# USB2CAN.net
KiCad netlist of a schematic drawn in Altium Designer
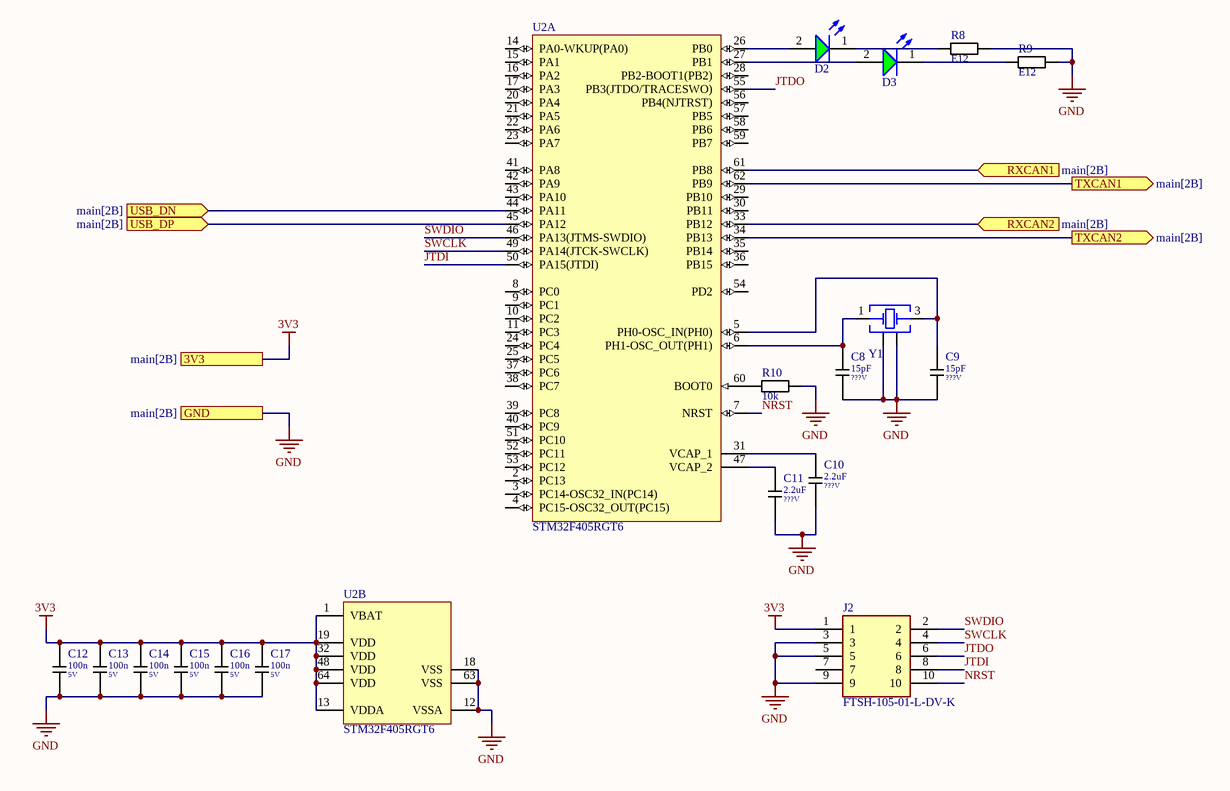
[diagram p0: USB2CAN.SchDoc]

(export (version "E")
  (design (tool "Eeschema 10.0.6"))
  (components
    (comp (ref "C8")
      (value "15pF")
      (footprint "0603_C")
      (description "Keramikkondensatoren 0603")
      (fields (field (name "SPG") "???V") (field (name "Comment") "15pF_???V"))
      (libsource (lib "Allgemeine_ETI_Schematic_Lib") (part "C_0603_Keramik"))
    )
    (comp (ref "C9")
      (value "15pF")
      (footprint "0603_C")
      (description "Keramikkondensatoren 0603")
      (fields (field (name "SPG") "???V") (field (name "Comment") "15pF_???V"))
      (libsource (lib "Allgemeine_ETI_Schematic_Lib") (part "C_0603_Keramik"))
    )
    (comp (ref "C10")
      (value "2.2uF")
      (footprint "0603_C")
      (description "Keramikkondensatoren 0603")
      (fields (field (name "SPG") "???V") (field (name "Comment") "2.2uF_???V"))
      (libsource (lib "Allgemeine_ETI_Schematic_Lib") (part "C_0603_Keramik"))
    )
    (comp (ref "C11")
      (value "2.2uF")
      (footprint "0603_C")
      (description "Keramikkondensatoren 0603")
      (fields (field (name "SPG") "???V") (field (name "Comment") "2.2uF_???V"))
      (libsource (lib "Allgemeine_ETI_Schematic_Lib") (part "C_0603_Keramik"))
    )
    (comp (ref "C12")
      (value "100n")
      (footprint "0603_C")
      (description "Keramikkondensatoren 0603")
      (fields (field (name "SPG") "5V") (field (name "Comment") "100n_5V"))
      (libsource (lib "Allgemeine_ETI_Schematic_Lib") (part "C_0603_Keramik"))
    )
    (comp (ref "C13")
      (value "100n")
      (footprint "0603_C")
      (description "Keramikkondensatoren 0603")
      (fields (field (name "SPG") "5V") (field (name "Comment") "100n_5V"))
      (libsource (lib "Allgemeine_ETI_Schematic_Lib") (part "C_0603_Keramik"))
    )
    (comp (ref "C14")
      (value "100n")
      (footprint "0603_C")
      (description "Keramikkondensatoren 0603")
      (fields (field (name "SPG") "5V") (field (name "Comment") "100n_5V"))
      (libsource (lib "Allgemeine_ETI_Schematic_Lib") (part "C_0603_Keramik"))
    )
    (comp (ref "C15")
      (value "100n")
      (footprint "0603_C")
      (description "Keramikkondensatoren 0603")
      (fields (field (name "SPG") "5V") (field (name "Comment") "100n_5V"))
      (libsource (lib "Allgemeine_ETI_Schematic_Lib") (part "C_0603_Keramik"))
    )
    (comp (ref "C16")
      (value "100n")
      (footprint "0603_C")
      (description "Keramikkondensatoren 0603")
      (fields (field (name "SPG") "5V") (field (name "Comment") "100n_5V"))
      (libsource (lib "Allgemeine_ETI_Schematic_Lib") (part "C_0603_Keramik"))
    )
    (comp (ref "C17")
      (value "100n")
      (footprint "0603_C")
      (description "Keramikkondensatoren 0603")
      (fields (field (name "SPG") "5V") (field (name "Comment") "100n_5V"))
      (libsource (lib "Allgemeine_ETI_Schematic_Lib") (part "C_0603_Keramik"))
    )
    (comp (ref "D2")
      (value "Bright Green, 2V, 140°")
      (footprint "WL-SMCD_0603")
      (description "WL-SMCD Mono-color Chip LED Diffused, SMT, size 0603, Bright Green, 2V, 140°")
      (fields
        (field (name "MANUFACTURER PART NUMBER") "150060VS55040")
        (field (name "MANUFACTURER") "Wurth Elektronik")
      )
      (libsource (lib "Altium_WL-SMCD (rev24a)") (part "150060VS55040"))
    )
    (comp (ref "D3")
      (value "Bright Green, 2V, 140°")
      (footprint "WL-SMCD_0603")
      (description "WL-SMCD Mono-color Chip LED Diffused, SMT, size 0603, Bright Green, 2V, 140°")
      (fields
        (field (name "MANUFACTURER PART NUMBER") "150060VS55040")
        (field (name "MANUFACTURER") "Wurth Elektronik")
      )
      (libsource (lib "Altium_WL-SMCD (rev24a)") (part "150060VS55040"))
    )
    (comp (ref "J2")
      (value "FTSH-105-01-L-DV-K")
      (footprint "FTSH10501LDVK:FTSH10501LDVK")
      (description "Samtec, FTSH, 10 Way, 2 Row, Straight Pin Header")
      (fields (field (name "MOUSER PART NUMBER") "200-FTSH10501LDVK"))
      (libsource (lib "FTSH-105-01-L-DV-K") (part "FTSH-105-01-L-DV-K"))
    )
    (comp (ref "R8")
      (value "E12")
      (footprint "0603_R")
      (description "R 0603, 75V, 0.1W")
      (libsource (lib "Allgemeine_ETI_Schematic_Lib") (part "R_0603"))
    )
    (comp (ref "R9")
      (value "E12")
      (footprint "0603_R")
      (description "R 0603, 75V, 0.1W")
      (libsource (lib "Allgemeine_ETI_Schematic_Lib") (part "R_0603"))
    )
    (comp (ref "R10")
      (value "10k")
      (footprint "0603_R")
      (description "R 0603, 75V, 0.1W")
      (libsource (lib "Allgemeine_ETI_Schematic_Lib") (part "R_0603"))
    )
    (comp (ref "U2")
      (value "STM32F405RGT6")
      (footprint "STM-LQFP64_N")
      (fields (field (name "MANUFACTURER") "STMicroelectronics"))
      (libsource (lib "STMicroelectronics STM32 F4") (part "STM32F405RGT6"))
    )
    (comp (ref "Y1")
      (value "8MHz")
      (footprint "WE-XTAL_CFPX-180")
      (description "WE-XTAL Quartz Crystal, SMT, CFPX-180, 8MHz, +/-30ppm")
      (fields
        (field (name "MANUFACTURER PART NUMBER") "830108313809")
        (field (name "MANUFACTURER") "Wurth Elektronik")
      )
      (libsource (lib "Altium_WE-XTAL (rev22a)") (part "830108313809"))
    )
  )
  (nets
    (net (code "1") (name "/JTDI") (class "Default")
      (node (ref "J2") (pin "8") (pinfunction "8_8") (pintype "passive"))
      (node (ref "U2") (pin "50") (pinfunction "PA15(JTDI)_50") (pintype "bidirectional"))
    )
    (net (code "2") (name "/JTDO") (class "Default")
      (node (ref "J2") (pin "6") (pinfunction "6_6") (pintype "passive"))
      (node (ref "U2") (pin "55") (pinfunction "PB3(JTDO/TRACESWO)_55") (pintype "bidirectional"))
    )
    (net (code "3") (name "/NRST") (class "Default")
      (node (ref "J2") (pin "10") (pinfunction "10_10") (pintype "passive"))
      (node (ref "U2") (pin "7") (pinfunction "NRST_7") (pintype "bidirectional"))
    )
    (net (code "4") (name "/RXCAN1") (class "Default")
      (node (ref "U2") (pin "61") (pinfunction "PB8_61") (pintype "bidirectional"))
    )
    (net (code "5") (name "/RXCAN2") (class "Default")
      (node (ref "U2") (pin "33") (pinfunction "PB12_33") (pintype "bidirectional"))
    )
    (net (code "6") (name "/SWCLK") (class "Default")
      (node (ref "J2") (pin "4") (pinfunction "4_4") (pintype "passive"))
      (node (ref "U2") (pin "49") (pinfunction "PA14(JTCK-SWCLK)_49") (pintype "bidirectional"))
    )
    (net (code "7") (name "/SWDIO") (class "Default")
      (node (ref "J2") (pin "2") (pinfunction "2_2") (pintype "passive"))
      (node (ref "U2") (pin "46") (pinfunction "PA13(JTMS-SWDIO)_46") (pintype "bidirectional"))
    )
    (net (code "8") (name "/TXCAN1") (class "Default")
      (node (ref "U2") (pin "62") (pinfunction "PB9_62") (pintype "bidirectional"))
    )
    (net (code "9") (name "/TXCAN2") (class "Default")
      (node (ref "U2") (pin "34") (pinfunction "PB13_34") (pintype "bidirectional"))
    )
    (net (code "10") (name "/USB_DN") (class "Default")
      (node (ref "U2") (pin "44") (pinfunction "PA11_44") (pintype "bidirectional"))
    )
    (net (code "11") (name "/USB_DP") (class "Default")
      (node (ref "U2") (pin "45") (pinfunction "PA12_45") (pintype "bidirectional"))
    )
    (net (code "12") (name "3V3") (class "Default")
      (node (ref "C12") (pin "1") (pinfunction "1_1") (pintype "passive"))
      (node (ref "C13") (pin "1") (pinfunction "1_1") (pintype "passive"))
      (node (ref "C14") (pin "1") (pinfunction "1_1") (pintype "passive"))
      (node (ref "C15") (pin "1") (pinfunction "1_1") (pintype "passive"))
      (node (ref "C16") (pin "1") (pinfunction "1_1") (pintype "passive"))
      (node (ref "C17") (pin "1") (pinfunction "1_1") (pintype "passive"))
      (node (ref "J2") (pin "1") (pinfunction "1_1") (pintype "passive"))
      (node (ref "U2") (pin "1") (pinfunction "VBAT_1") (pintype "power_in"))
      (node (ref "U2") (pin "13") (pinfunction "VDDA_13") (pintype "power_in"))
      (node (ref "U2") (pin "19") (pinfunction "VDD_19") (pintype "power_in"))
      (node (ref "U2") (pin "32") (pinfunction "VDD_32") (pintype "power_in"))
      (node (ref "U2") (pin "48") (pinfunction "VDD_48") (pintype "power_in"))
      (node (ref "U2") (pin "64") (pinfunction "VDD_64") (pintype "power_in"))
    )
    (net (code "13") (name "GND") (class "Default")
      (node (ref "C10") (pin "2") (pinfunction "2_2") (pintype "passive"))
      (node (ref "C11") (pin "2") (pinfunction "2_2") (pintype "passive"))
      (node (ref "C12") (pin "2") (pinfunction "2_2") (pintype "passive"))
      (node (ref "C13") (pin "2") (pinfunction "2_2") (pintype "passive"))
      (node (ref "C14") (pin "2") (pinfunction "2_2") (pintype "passive"))
      (node (ref "C15") (pin "2") (pinfunction "2_2") (pintype "passive"))
      (node (ref "C16") (pin "2") (pinfunction "2_2") (pintype "passive"))
      (node (ref "C17") (pin "2") (pinfunction "2_2") (pintype "passive"))
      (node (ref "C8") (pin "2") (pinfunction "2_2") (pintype "passive"))
      (node (ref "C9") (pin "2") (pinfunction "2_2") (pintype "passive"))
      (node (ref "J2") (pin "3") (pinfunction "3_3") (pintype "passive"))
      (node (ref "J2") (pin "5") (pinfunction "5_5") (pintype "passive"))
      (node (ref "J2") (pin "9") (pinfunction "9_9") (pintype "passive"))
      (node (ref "R10") (pin "2") (pinfunction "2_2") (pintype "passive"))
      (node (ref "R8") (pin "2") (pinfunction "2_2") (pintype "passive"))
      (node (ref "R9") (pin "2") (pinfunction "2_2") (pintype "passive"))
      (node (ref "U2") (pin "12") (pinfunction "VSSA_12") (pintype "power_in"))
      (node (ref "U2") (pin "18") (pinfunction "VSS_18") (pintype "power_in"))
      (node (ref "U2") (pin "63") (pinfunction "VSS_63") (pintype "power_in"))
      (node (ref "Y1") (pin "2") (pinfunction "GND&Lid_2") (pintype "passive"))
      (node (ref "Y1") (pin "4") (pinfunction "GND&Lid_4") (pintype "passive"))
    )
    (net (code "14") (name "Net-(D2-A)") (class "Default")
      (node (ref "D2") (pin "2") (pinfunction "A_2") (pintype "passive"))
      (node (ref "U2") (pin "26") (pinfunction "PB0_26") (pintype "bidirectional"))
    )
    (net (code "15") (name "Net-(D2-K)") (class "Default")
      (node (ref "D2") (pin "1") (pinfunction "K_1") (pintype "passive"))
      (node (ref "R8") (pin "1") (pinfunction "1_1") (pintype "passive"))
    )
    (net (code "16") (name "Net-(D3-A)") (class "Default")
      (node (ref "D3") (pin "2") (pinfunction "A_2") (pintype "passive"))
      (node (ref "U2") (pin "27") (pinfunction "PB1_27") (pintype "bidirectional"))
    )
    (net (code "17") (name "Net-(D3-K)") (class "Default")
      (node (ref "D3") (pin "1") (pinfunction "K_1") (pintype "passive"))
      (node (ref "R9") (pin "1") (pinfunction "1_1") (pintype "passive"))
    )
    (net (code "18") (name "Net-(U2A-BOOT0)") (class "Default")
      (node (ref "R10") (pin "1") (pinfunction "1_1") (pintype "passive"))
      (node (ref "U2") (pin "60") (pinfunction "BOOT0_60") (pintype "input"))
    )
    (net (code "19") (name "Net-(U2A-PH0-OSC_IN(PH0))") (class "Default")
      (node (ref "C9") (pin "1") (pinfunction "1_1") (pintype "passive"))
      (node (ref "U2") (pin "5") (pinfunction "PH0-OSC_IN(PH0)_5") (pintype "bidirectional"))
      (node (ref "Y1") (pin "3") (pinfunction "Crystal_3") (pintype "passive"))
    )
    (net (code "20") (name "Net-(U2A-PH1-OSC_OUT(PH1))") (class "Default")
      (node (ref "C8") (pin "1") (pinfunction "1_1") (pintype "passive"))
      (node (ref "U2") (pin "6") (pinfunction "PH1-OSC_OUT(PH1)_6") (pintype "bidirectional"))
      (node (ref "Y1") (pin "1") (pinfunction "Crystal_1") (pintype "passive"))
    )
    (net (code "21") (name "Net-(U2A-VCAP_1)") (class "Default")
      (node (ref "C10") (pin "1") (pinfunction "1_1") (pintype "passive"))
      (node (ref "U2") (pin "31") (pinfunction "VCAP_1_31") (pintype "power_in"))
    )
    (net (code "22") (name "Net-(U2A-VCAP_2)") (class "Default")
      (node (ref "C11") (pin "1") (pinfunction "1_1") (pintype "passive"))
      (node (ref "U2") (pin "47") (pinfunction "VCAP_2_47") (pintype "power_in"))
    )
    (net (code "23") (name "unconnected-(J2-Pad7)") (class "Default")
      (node (ref "J2") (pin "7") (pinfunction "7_7") (pintype "passive"))
    )
    (net (code "24") (name "unconnected-(U2A-PA0-WKUP(PA0)-Pad14)") (class "Default")
      (node (ref "U2") (pin "14") (pinfunction "PA0-WKUP(PA0)_14") (pintype "bidirectional"))
    )
    (net (code "25") (name "unconnected-(U2A-PA1-Pad15)") (class "Default")
      (node (ref "U2") (pin "15") (pinfunction "PA1_15") (pintype "bidirectional"))
    )
    (net (code "26") (name "unconnected-(U2A-PA2-Pad16)") (class "Default")
      (node (ref "U2") (pin "16") (pinfunction "PA2_16") (pintype "bidirectional"))
    )
    (net (code "27") (name "unconnected-(U2A-PA3-Pad17)") (class "Default")
      (node (ref "U2") (pin "17") (pinfunction "PA3_17") (pintype "bidirectional"))
    )
    (net (code "28") (name "unconnected-(U2A-PA4-Pad20)") (class "Default")
      (node (ref "U2") (pin "20") (pinfunction "PA4_20") (pintype "bidirectional"))
    )
    (net (code "29") (name "unconnected-(U2A-PA5-Pad21)") (class "Default")
      (node (ref "U2") (pin "21") (pinfunction "PA5_21") (pintype "bidirectional"))
    )
    (net (code "30") (name "unconnected-(U2A-PA6-Pad22)") (class "Default")
      (node (ref "U2") (pin "22") (pinfunction "PA6_22") (pintype "bidirectional"))
    )
    (net (code "31") (name "unconnected-(U2A-PA7-Pad23)") (class "Default")
      (node (ref "U2") (pin "23") (pinfunction "PA7_23") (pintype "bidirectional"))
    )
    (net (code "32") (name "unconnected-(U2A-PA8-Pad41)") (class "Default")
      (node (ref "U2") (pin "41") (pinfunction "PA8_41") (pintype "bidirectional"))
    )
    (net (code "33") (name "unconnected-(U2A-PA9-Pad42)") (class "Default")
      (node (ref "U2") (pin "42") (pinfunction "PA9_42") (pintype "bidirectional"))
    )
    (net (code "34") (name "unconnected-(U2A-PA10-Pad43)") (class "Default")
      (node (ref "U2") (pin "43") (pinfunction "PA10_43") (pintype "bidirectional"))
    )
    (net (code "35") (name "unconnected-(U2A-PB2-BOOT1(PB2)-Pad28)") (class "Default")
      (node (ref "U2") (pin "28") (pinfunction "PB2-BOOT1(PB2)_28") (pintype "bidirectional"))
    )
    (net (code "36") (name "unconnected-(U2A-PB4(NJTRST)-Pad56)") (class "Default")
      (node (ref "U2") (pin "56") (pinfunction "PB4(NJTRST)_56") (pintype "bidirectional"))
    )
    (net (code "37") (name "unconnected-(U2A-PB5-Pad57)") (class "Default")
      (node (ref "U2") (pin "57") (pinfunction "PB5_57") (pintype "bidirectional"))
    )
    (net (code "38") (name "unconnected-(U2A-PB6-Pad58)") (class "Default")
      (node (ref "U2") (pin "58") (pinfunction "PB6_58") (pintype "bidirectional"))
    )
    (net (code "39") (name "unconnected-(U2A-PB7-Pad59)") (class "Default")
      (node (ref "U2") (pin "59") (pinfunction "PB7_59") (pintype "bidirectional"))
    )
    (net (code "40") (name "unconnected-(U2A-PB10-Pad29)") (class "Default")
      (node (ref "U2") (pin "29") (pinfunction "PB10_29") (pintype "bidirectional"))
    )
    (net (code "41") (name "unconnected-(U2A-PB11-Pad30)") (class "Default")
      (node (ref "U2") (pin "30") (pinfunction "PB11_30") (pintype "bidirectional"))
    )
    (net (code "42") (name "unconnected-(U2A-PB14-Pad35)") (class "Default")
      (node (ref "U2") (pin "35") (pinfunction "PB14_35") (pintype "bidirectional"))
    )
    (net (code "43") (name "unconnected-(U2A-PB15-Pad36)") (class "Default")
      (node (ref "U2") (pin "36") (pinfunction "PB15_36") (pintype "bidirectional"))
    )
    (net (code "44") (name "unconnected-(U2A-PC0-Pad8)") (class "Default")
      (node (ref "U2") (pin "8") (pinfunction "PC0_8") (pintype "bidirectional"))
    )
    (net (code "45") (name "unconnected-(U2A-PC1-Pad9)") (class "Default")
      (node (ref "U2") (pin "9") (pinfunction "PC1_9") (pintype "bidirectional"))
    )
    (net (code "46") (name "unconnected-(U2A-PC2-Pad10)") (class "Default")
      (node (ref "U2") (pin "10") (pinfunction "PC2_10") (pintype "bidirectional"))
    )
    (net (code "47") (name "unconnected-(U2A-PC3-Pad11)") (class "Default")
      (node (ref "U2") (pin "11") (pinfunction "PC3_11") (pintype "bidirectional"))
    )
    (net (code "48") (name "unconnected-(U2A-PC4-Pad24)") (class "Default")
      (node (ref "U2") (pin "24") (pinfunction "PC4_24") (pintype "bidirectional"))
    )
    (net (code "49") (name "unconnected-(U2A-PC5-Pad25)") (class "Default")
      (node (ref "U2") (pin "25") (pinfunction "PC5_25") (pintype "bidirectional"))
    )
    (net (code "50") (name "unconnected-(U2A-PC6-Pad37)") (class "Default")
      (node (ref "U2") (pin "37") (pinfunction "PC6_37") (pintype "bidirectional"))
    )
    (net (code "51") (name "unconnected-(U2A-PC7-Pad38)") (class "Default")
      (node (ref "U2") (pin "38") (pinfunction "PC7_38") (pintype "bidirectional"))
    )
    (net (code "52") (name "unconnected-(U2A-PC8-Pad39)") (class "Default")
      (node (ref "U2") (pin "39") (pinfunction "PC8_39") (pintype "bidirectional"))
    )
    (net (code "53") (name "unconnected-(U2A-PC9-Pad40)") (class "Default")
      (node (ref "U2") (pin "40") (pinfunction "PC9_40") (pintype "bidirectional"))
    )
    (net (code "54") (name "unconnected-(U2A-PC10-Pad51)") (class "Default")
      (node (ref "U2") (pin "51") (pinfunction "PC10_51") (pintype "bidirectional"))
    )
    (net (code "55") (name "unconnected-(U2A-PC11-Pad52)") (class "Default")
      (node (ref "U2") (pin "52") (pinfunction "PC11_52") (pintype "bidirectional"))
    )
    (net (code "56") (name "unconnected-(U2A-PC12-Pad53)") (class "Default")
      (node (ref "U2") (pin "53") (pinfunction "PC12_53") (pintype "bidirectional"))
    )
    (net (code "57") (name "unconnected-(U2A-PC13-Pad2)") (class "Default")
      (node (ref "U2") (pin "2") (pinfunction "PC13_2") (pintype "bidirectional"))
    )
    (net (code "58") (name "unconnected-(U2A-PC14-OSC32_IN(PC14)-Pad3)") (class "Default")
      (node (ref "U2") (pin "3") (pinfunction "PC14-OSC32_IN(PC14)_3") (pintype "bidirectional"))
    )
    (net (code "59") (name "unconnected-(U2A-PC15-OSC32_OUT(PC15)-Pad4)") (class "Default")
      (node (ref "U2") (pin "4") (pinfunction "PC15-OSC32_OUT(PC15)_4") (pintype "bidirectional"))
    )
    (net (code "60") (name "unconnected-(U2A-PD2-Pad54)") (class "Default")
      (node (ref "U2") (pin "54") (pinfunction "PD2_54") (pintype "bidirectional"))
    )
  )
)
